# lcd1601.net
KiCad netlist of a schematic drawn in EasyEDA Pro
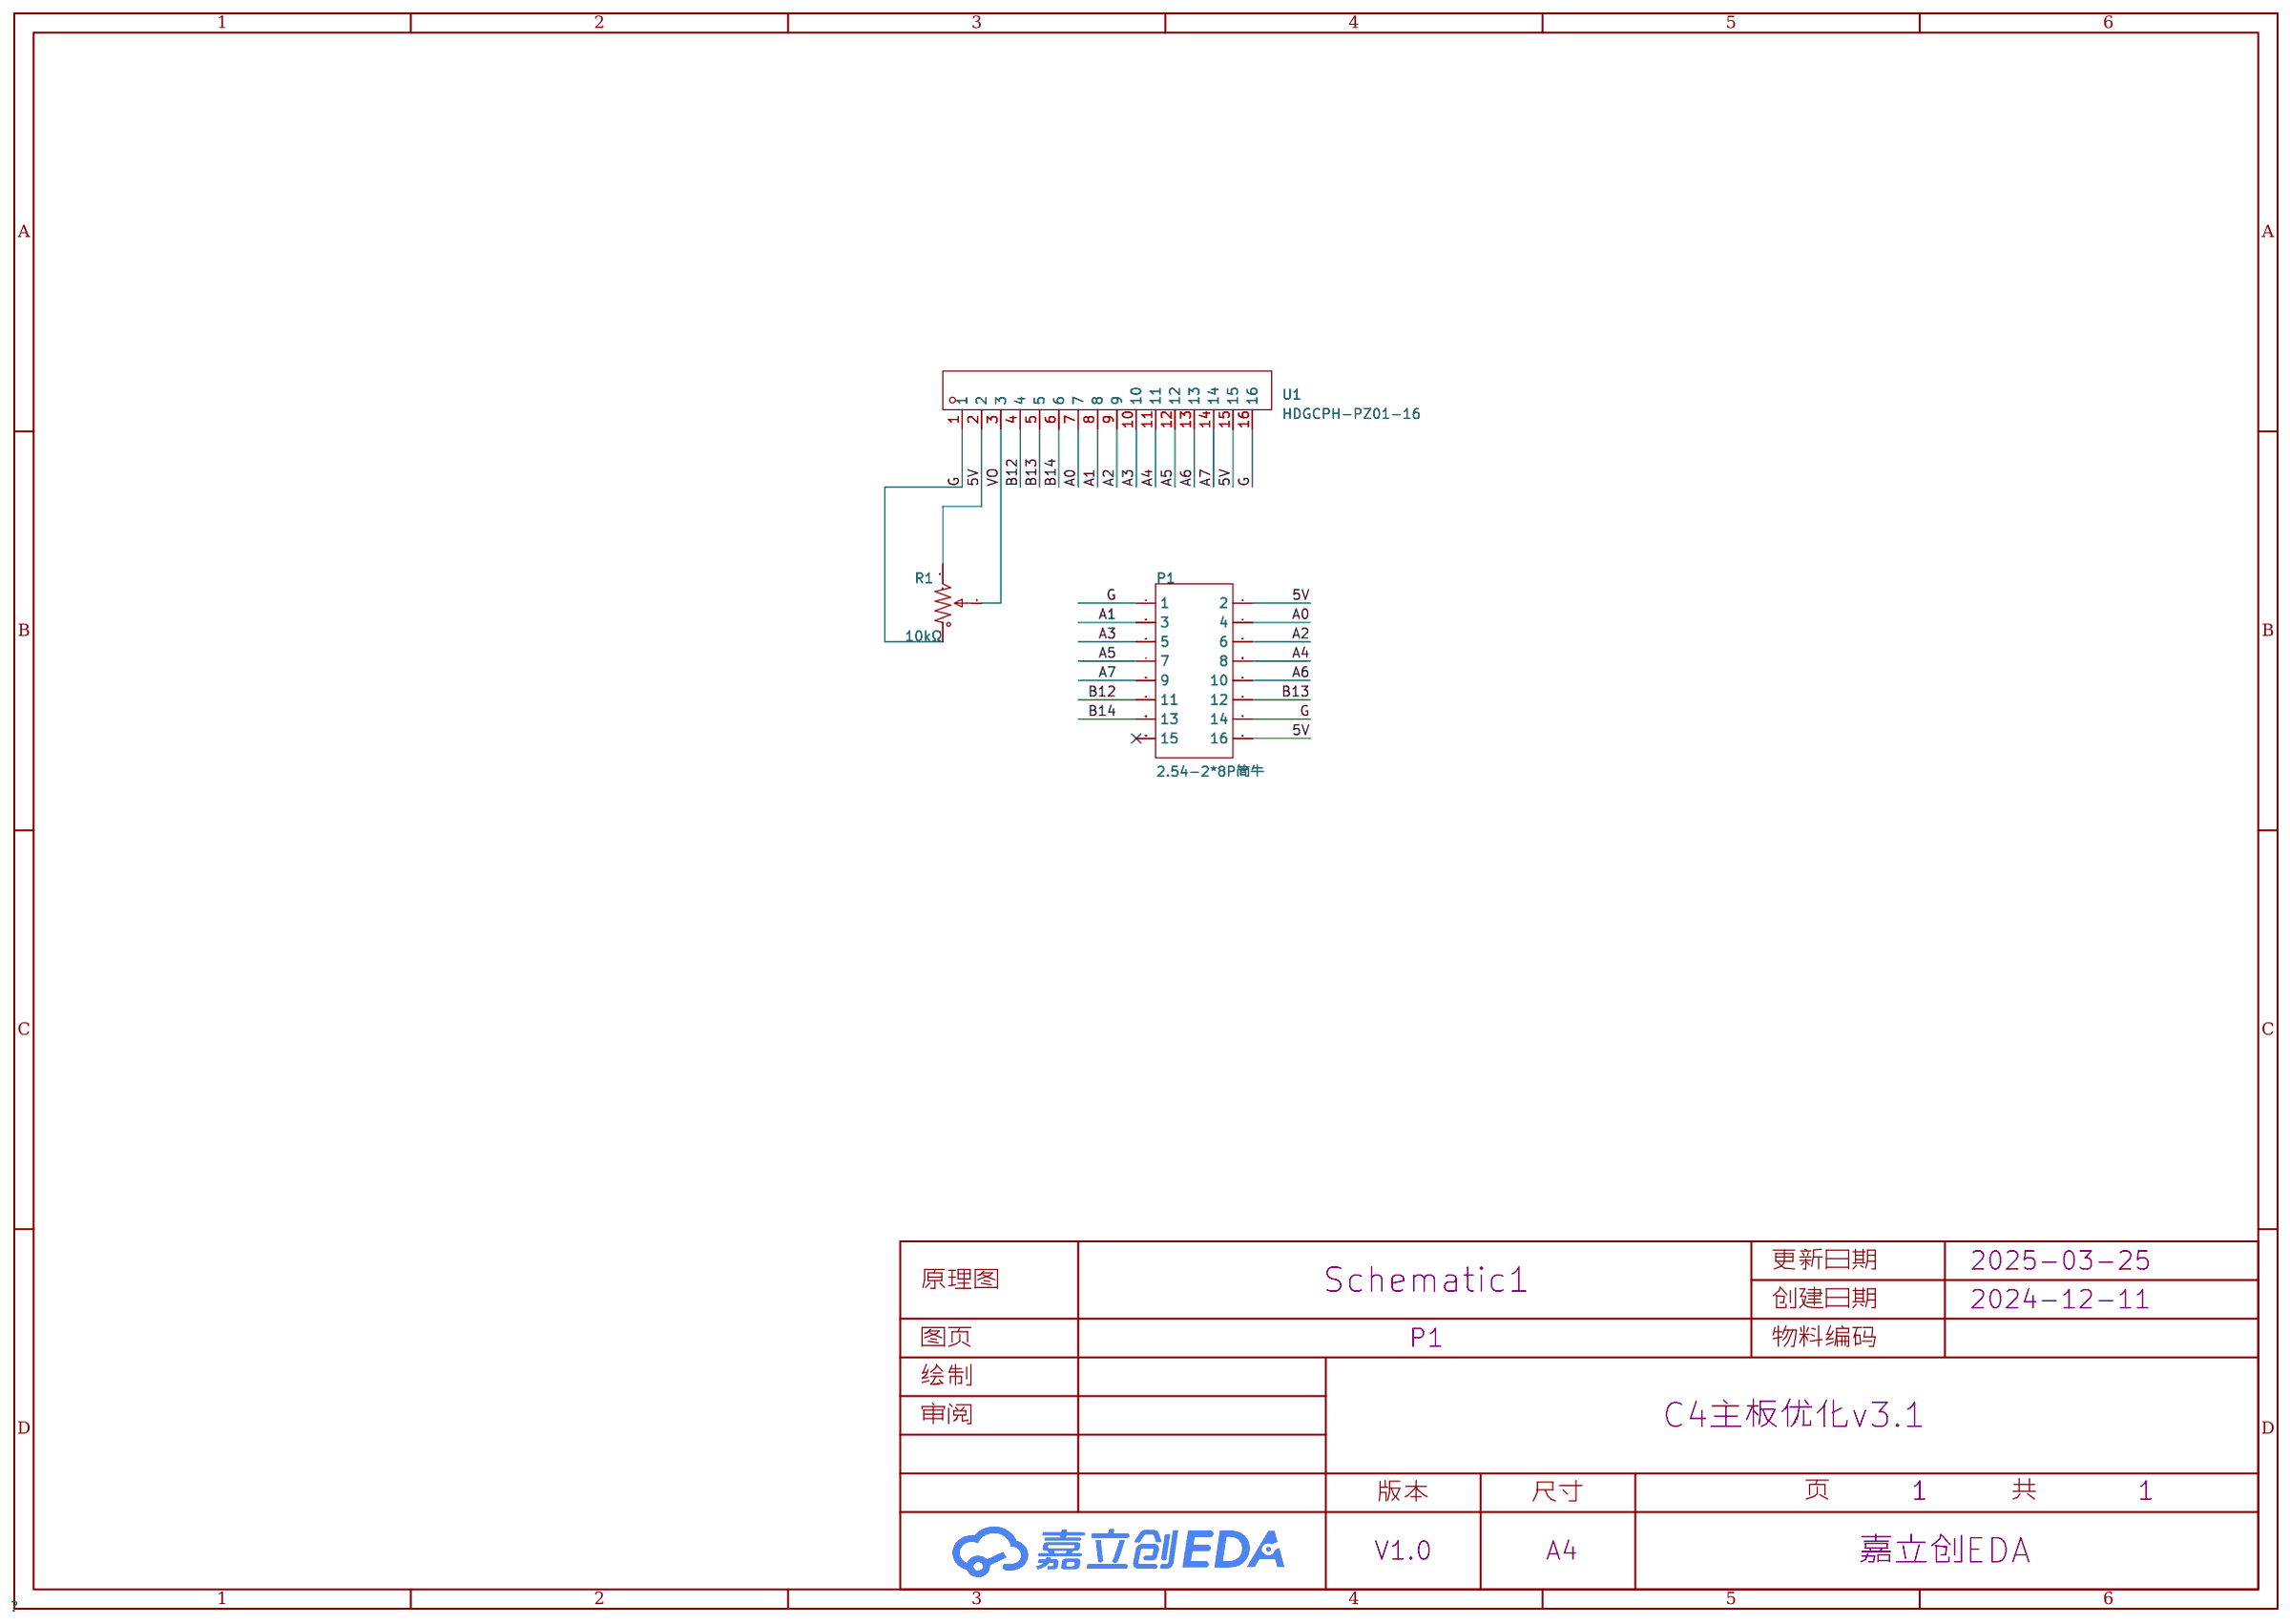
[diagram p0: schematic sheet]

(export (version "E")
  (design (tool "Eeschema 10.0.6"))
  (components
    (comp (ref "P1")
      (value "2.54-2*8P简牛")
      (footprint "easyedapro:IDC-TH_16P-P2.54_C3406")
      (description "连接器类型:简牛座;间距:2.54mm;结构:2x8P;封装形式:直插;行距:2.54mm;排数:2;每排PIN数:8;触头材质:-;触头镀层:-;")
      (fields (field (name "Manufacturer") "BOOMELE(博穆精密)"))
      (libsource (lib "easyedapro") (part "HDR-IDC-2.54-2X8P"))
    )
    (comp (ref "R1")
      (value "10kΩ")
      (footprint "easyedapro:RES-ADJ-TH_3362P")
      (description "阻值:10kΩ;精度:±10%;")
      (fields (field (name "Manufacturer Part") "3362P-1-103") (field (name "Manufacturer") "BOCHEN(博晨)"))
      (libsource (lib "easyedapro") (part "3362P-1-103_C118956"))
    )
    (comp (ref "U1")
      (value "HDGCPH-PZ01-16")
      (footprint "easyedapro:HDR-TH_16P-P2.54-V-M_1")
      (fields (field (name "Manufacturer") "HDGC(华德共创)"))
      (libsource (lib "easyedapro") (part "HDGCPH-PZ01-16"))
    )
  )
  (nets
    (net (code "1") (name "/5V") (class "Default")
      (node (ref "P1") (pin "16") (pinfunction "16_16") (pintype "unspecified"))
      (node (ref "P1") (pin "2") (pinfunction "2_2") (pintype "unspecified"))
      (node (ref "R1") (pin "3") (pinfunction "3_3") (pintype "unspecified"))
      (node (ref "U1") (pin "15") (pinfunction "15_15") (pintype "unspecified"))
      (node (ref "U1") (pin "2") (pinfunction "2_2") (pintype "unspecified"))
    )
    (net (code "2") (name "/A0") (class "Default")
      (node (ref "P1") (pin "4") (pinfunction "4_4") (pintype "unspecified"))
      (node (ref "U1") (pin "7") (pinfunction "7_7") (pintype "unspecified"))
    )
    (net (code "3") (name "/A1") (class "Default")
      (node (ref "P1") (pin "3") (pinfunction "3_3") (pintype "unspecified"))
      (node (ref "U1") (pin "8") (pinfunction "8_8") (pintype "unspecified"))
    )
    (net (code "4") (name "/A2") (class "Default")
      (node (ref "P1") (pin "6") (pinfunction "6_6") (pintype "unspecified"))
      (node (ref "U1") (pin "9") (pinfunction "9_9") (pintype "unspecified"))
    )
    (net (code "5") (name "/A3") (class "Default")
      (node (ref "P1") (pin "5") (pinfunction "5_5") (pintype "unspecified"))
      (node (ref "U1") (pin "10") (pinfunction "10_10") (pintype "unspecified"))
    )
    (net (code "6") (name "/A4") (class "Default")
      (node (ref "P1") (pin "8") (pinfunction "8_8") (pintype "unspecified"))
      (node (ref "U1") (pin "11") (pinfunction "11_11") (pintype "unspecified"))
    )
    (net (code "7") (name "/A5") (class "Default")
      (node (ref "P1") (pin "7") (pinfunction "7_7") (pintype "unspecified"))
      (node (ref "U1") (pin "12") (pinfunction "12_12") (pintype "unspecified"))
    )
    (net (code "8") (name "/A6") (class "Default")
      (node (ref "P1") (pin "10") (pinfunction "10_10") (pintype "unspecified"))
      (node (ref "U1") (pin "13") (pinfunction "13_13") (pintype "unspecified"))
    )
    (net (code "9") (name "/A7") (class "Default")
      (node (ref "P1") (pin "9") (pinfunction "9_9") (pintype "unspecified"))
      (node (ref "U1") (pin "14") (pinfunction "14_14") (pintype "unspecified"))
    )
    (net (code "10") (name "/B12") (class "Default")
      (node (ref "P1") (pin "11") (pinfunction "11_11") (pintype "unspecified"))
      (node (ref "U1") (pin "4") (pinfunction "4_4") (pintype "unspecified"))
    )
    (net (code "11") (name "/B13") (class "Default")
      (node (ref "P1") (pin "12") (pinfunction "12_12") (pintype "unspecified"))
      (node (ref "U1") (pin "5") (pinfunction "5_5") (pintype "unspecified"))
    )
    (net (code "12") (name "/B14") (class "Default")
      (node (ref "P1") (pin "13") (pinfunction "13_13") (pintype "unspecified"))
      (node (ref "U1") (pin "6") (pinfunction "6_6") (pintype "unspecified"))
    )
    (net (code "13") (name "/G") (class "Default")
      (node (ref "P1") (pin "1") (pinfunction "1_1") (pintype "unspecified"))
      (node (ref "P1") (pin "14") (pinfunction "14_14") (pintype "unspecified"))
      (node (ref "R1") (pin "1") (pinfunction "1_1") (pintype "unspecified"))
      (node (ref "U1") (pin "1") (pinfunction "1_1") (pintype "unspecified"))
      (node (ref "U1") (pin "16") (pinfunction "16_16") (pintype "unspecified"))
    )
    (net (code "14") (name "/VO") (class "Default")
      (node (ref "R1") (pin "2") (pinfunction "2_2") (pintype "unspecified"))
      (node (ref "U1") (pin "3") (pinfunction "3_3") (pintype "unspecified"))
    )
    (net (code "15") (name "unconnected-(P1-Pad15)") (class "Default")
      (node (ref "P1") (pin "15") (pinfunction "15_15") (pintype "unspecified+no_connect"))
    )
  )
)
